# MCU.net
KiCad netlist of a schematic drawn in Altium Designer
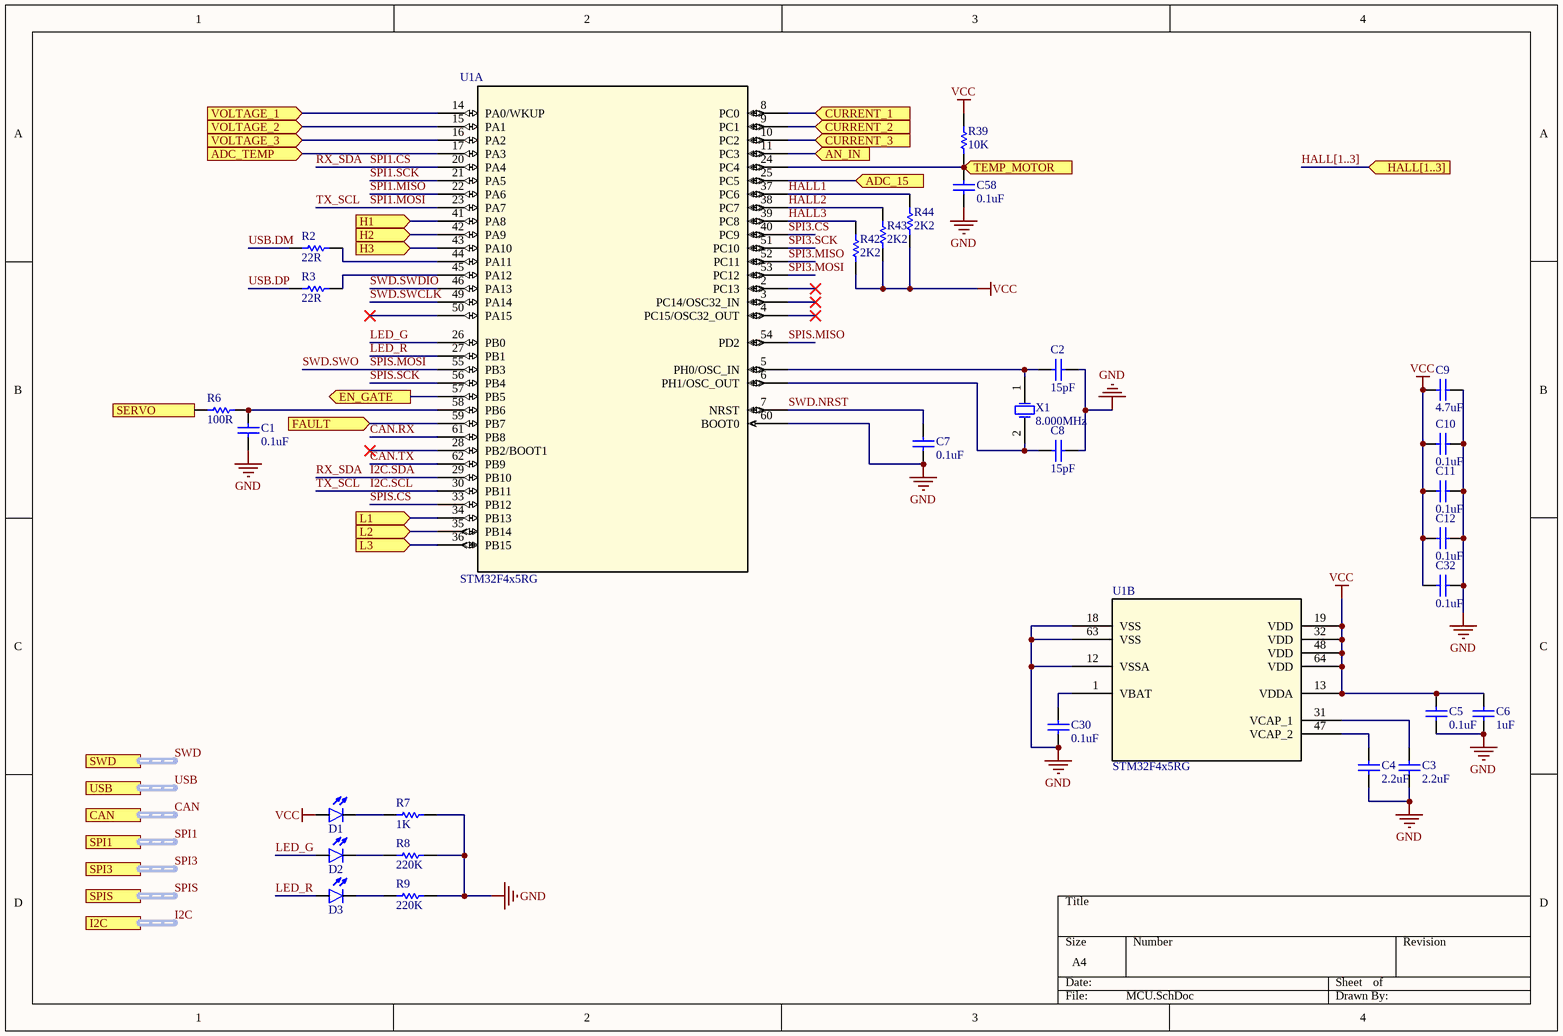
[diagram p0: MCU.SchDoc]

(export (version "E")
  (design (tool "Eeschema 10.0.6"))
  (components
    (comp (ref "C1")
      (value "0.1uF")
      (footprint "C0603[1608X92]")
      (description "0.1uF 16V 10% 0603 (1608 Metric)")
      (fields (field (name "PARTNUMBER") "GCM188R71C104KA37D") (field (name "MANUFACTURER") "Murata"))
      (libsource (lib "Capacitors") (part "CAP_0.1uF_16V_0603_10%"))
    )
    (comp (ref "C2")
      (value "15pF")
      (footprint "C0603[1608X92]")
      (description "15pF 6.3V 1% 0603 (1608 Metric)")
      (fields (field (name "PARTNUMBER") "CBR02C150F9GAC") (field (name "MANUFACTURER") "KEMET"))
      (libsource (lib "Capacitors") (part "CAP_15pF_6.3V_0603_1%"))
    )
    (comp (ref "C3")
      (value "2.2uF")
      (footprint "C1206[3216X160]")
      (description "2.2uF 6.3V 10% 1206 (3216 Metric)")
      (fields (field (name "PARTNUMBER") "GRM31CR60J476KE19L") (field (name "MANUFACTURER") "Murata"))
      (libsource (lib "Capacitors") (part "CAP_2.2uF_16V_1206_10%"))
    )
    (comp (ref "C4")
      (value "2.2uF")
      (footprint "C1206[3216X160]")
      (description "2.2uF 6.3V 10% 1206 (3216 Metric)")
      (fields (field (name "PARTNUMBER") "GRM31CR60J476KE19L") (field (name "MANUFACTURER") "Murata"))
      (libsource (lib "Capacitors") (part "CAP_2.2uF_16V_1206_10%"))
    )
    (comp (ref "C5")
      (value "0.1uF")
      (footprint "C0603[1608X92]")
      (description "0.1uF 6.3V 10% 0603 (1608 Metric)")
      (fields (field (name "PARTNUMBER") "GRM188R70J104KA01D") (field (name "MANUFACTURER") "Murata"))
      (libsource (lib "Capacitors") (part "CAP_0.1uF_6.3V_0603_10%"))
    )
    (comp (ref "C6")
      (value "1uF")
      (footprint "C0603[1608X92]")
      (description "1uF 6.3V 10% 0603 (1608 Metric)")
      (fields (field (name "PARTNUMBER") "GRM188R60J105KA01D") (field (name "MANUFACTURER") "Murata"))
      (libsource (lib "Capacitors") (part "CAP_1uF_6.3V_0603_10%"))
    )
    (comp (ref "C7")
      (value "0.1uF")
      (footprint "C0603[1608X92]")
      (description "0.1uF 6.3V 10% 0603 (1608 Metric)")
      (fields (field (name "PARTNUMBER") "GRM188R70J104KA01D") (field (name "MANUFACTURER") "Murata"))
      (libsource (lib "Capacitors") (part "CAP_0.1uF_6.3V_0603_10%"))
    )
    (comp (ref "C8")
      (value "15pF")
      (footprint "C0603[1608X92]")
      (description "15pF 6.3V 1% 0603 (1608 Metric)")
      (fields (field (name "PARTNUMBER") "CBR02C150F9GAC") (field (name "MANUFACTURER") "KEMET"))
      (libsource (lib "Capacitors") (part "CAP_15pF_6.3V_0603_1%"))
    )
    (comp (ref "C9")
      (value "4.7uF")
      (footprint "C0603[1608X92]")
      (description "4.7uF 6.3V 10% 0603 (1608 Metric)")
      (fields (field (name "PARTNUMBER") "GRM188R60J475KE19D") (field (name "MANUFACTURER") "Murata"))
      (libsource (lib "Capacitors") (part "CAP_4.7uF_6.3V_0603_10%"))
    )
    (comp (ref "C10")
      (value "0.1uF")
      (footprint "C0603[1608X92]")
      (description "0.1uF 6.3V 10% 0603 (1608 Metric)")
      (fields (field (name "PARTNUMBER") "GRM188R70J104KA01D") (field (name "MANUFACTURER") "Murata"))
      (libsource (lib "Capacitors") (part "CAP_0.1uF_6.3V_0603_10%"))
    )
    (comp (ref "C11")
      (value "0.1uF")
      (footprint "C0603[1608X92]")
      (description "0.1uF 6.3V 10% 0603 (1608 Metric)")
      (fields (field (name "PARTNUMBER") "GRM188R70J104KA01D") (field (name "MANUFACTURER") "Murata"))
      (libsource (lib "Capacitors") (part "CAP_0.1uF_6.3V_0603_10%"))
    )
    (comp (ref "C12")
      (value "0.1uF")
      (footprint "C0603[1608X92]")
      (description "0.1uF 6.3V 10% 0603 (1608 Metric)")
      (fields (field (name "PARTNUMBER") "GRM188R70J104KA01D") (field (name "MANUFACTURER") "Murata"))
      (libsource (lib "Capacitors") (part "CAP_0.1uF_6.3V_0603_10%"))
    )
    (comp (ref "C30")
      (value "0.1uF")
      (footprint "C0603[1608X92]")
      (description "0.1uF 6.3V 10% 0603 (1608 Metric)")
      (fields (field (name "PARTNUMBER") "GRM188R70J104KA01D") (field (name "MANUFACTURER") "Murata"))
      (libsource (lib "Capacitors") (part "CAP_0.1uF_6.3V_0603_10%"))
    )
    (comp (ref "C32")
      (value "0.1uF")
      (footprint "C0603[1608X92]")
      (description "0.1uF 6.3V 10% 0603 (1608 Metric)")
      (fields (field (name "PARTNUMBER") "GRM188R70J104KA01D") (field (name "MANUFACTURER") "Murata"))
      (libsource (lib "Capacitors") (part "CAP_0.1uF_6.3V_0603_10%"))
    )
    (comp (ref "C58")
      (value "0.1uF")
      (footprint "C0603[1608X92]")
      (description "0.1uF 6.3V 10% 0603 (1608 Metric)")
      (fields (field (name "PARTNUMBER") "GRM188R70J104KA01D") (field (name "MANUFACTURER") "Murata"))
      (libsource (lib "Capacitors") (part "CAP_0.1uF_6.3V_0603_10%"))
    )
    (comp (ref "D1")
      (value "LED_0603_BLUE_5mA")
      (footprint "LED0603")
      (fields (field (name "PARTNUMBER") "LTST-C193TBKT-5A") (field (name "MANUFACTURER") "Lite-On Inc."))
      (libsource (lib "LEDs") (part "LED_0603_BLUE_5mA"))
    )
    (comp (ref "D2")
      (value "LED_0603_GREEN_5mA")
      (footprint "LED0603")
      (fields (field (name "PARTNUMBER") "LTST-C193TGKT-5A") (field (name "MANUFACTURER") "Lite-On Inc."))
      (libsource (lib "LEDs") (part "LED_0603_GREEN_5mA"))
    )
    (comp (ref "D3")
      (value "LED_0603_ORANGE_5mA")
      (footprint "LED0603")
      (fields (field (name "PARTNUMBER") "LTST-C193KFKT-5A") (field (name "MANUFACTURER") "Lite-On Inc."))
      (libsource (lib "LEDs") (part "LED_0603_ORANGE_5mA"))
    )
    (comp (ref "R2")
      (value "22R")
      (footprint "R0603[1608]")
      (description "22R 0.25W 1% 0603 (1005 Metric)")
      (fields (field (name "MANUFACTURER") "Vishay / Dale") (field (name "PARTNUMBER") "CRCW060322R0FKEAHP"))
      (libsource (lib "Resistors") (part "RES_22R_0603_1%"))
    )
    (comp (ref "R3")
      (value "22R")
      (footprint "R0603[1608]")
      (description "22R 0.25W 1% 0603 (1005 Metric)")
      (fields (field (name "MANUFACTURER") "Vishay / Dale") (field (name "PARTNUMBER") "CRCW060322R0FKEAHP"))
      (libsource (lib "Resistors") (part "RES_22R_0603_1%"))
    )
    (comp (ref "R6")
      (value "100R")
      (footprint "R0603[1608]")
      (description "100R 0.25W 1% 0603 (1005 Metric)")
      (fields (field (name "MANUFACTURER") "Vishay / Dale") (field (name "PARTNUMBER") "CRCW0603100RFKEAHP"))
      (libsource (lib "Resistors") (part "RES_100R_0603_1%"))
    )
    (comp (ref "R7")
      (value "1K")
      (footprint "R0603[1608]")
      (description "1K 0.25W 1% 0603 (1005 Metric)")
      (fields (field (name "MANUFACTURER") "Vishay / Dale") (field (name "PARTNUMBER") "CRCW06031K00FKEAHP"))
      (libsource (lib "Resistors") (part "RES_1K_0603_1%"))
    )
    (comp (ref "R8")
      (value "220K")
      (footprint "R0603[1608]")
      (description "220K 0.25W 1% 0603 (1005 Metric)")
      (fields (field (name "MANUFACTURER") "Vishay / Dale") (field (name "PARTNUMBER") "CRCW0603220KJNEAHP"))
      (libsource (lib "Resistors") (part "RES_220K_0603_1%"))
    )
    (comp (ref "R9")
      (value "220K")
      (footprint "R0603[1608]")
      (description "220K 0.25W 1% 0603 (1005 Metric)")
      (fields (field (name "MANUFACTURER") "Vishay / Dale") (field (name "PARTNUMBER") "CRCW0603220KJNEAHP"))
      (libsource (lib "Resistors") (part "RES_220K_0603_1%"))
    )
    (comp (ref "R39")
      (value "10K")
      (footprint "R0603[1608]")
      (description "10K 0.25W 1% 0603 (1005 Metric)")
      (fields (field (name "MANUFACTURER") "Vishay") (field (name "PARTNUMBER") "RCS060310K0FKEA"))
      (libsource (lib "Resistors") (part "RES_10K_0603_1%"))
    )
    (comp (ref "R42")
      (value "2K2")
      (footprint "R0603[1608]")
      (description "2K2 0.25W 1% 0603 (1005 Metric)")
      (fields (field (name "MANUFACTURER") "Vishay / Dale") (field (name "PARTNUMBER") "CRCW06032K20FKEAHP"))
      (libsource (lib "Resistors") (part "RES_2K2_0603_1%"))
    )
    (comp (ref "R43")
      (value "2K2")
      (footprint "R0603[1608]")
      (description "2K2 0.25W 1% 0603 (1005 Metric)")
      (fields (field (name "MANUFACTURER") "Vishay / Dale") (field (name "PARTNUMBER") "CRCW06032K20FKEAHP"))
      (libsource (lib "Resistors") (part "RES_2K2_0603_1%"))
    )
    (comp (ref "R44")
      (value "2K2")
      (footprint "R0603[1608]")
      (description "2K2 0.25W 1% 0603 (1005 Metric)")
      (fields (field (name "MANUFACTURER") "Vishay / Dale") (field (name "PARTNUMBER") "CRCW06032K20FKEAHP"))
      (libsource (lib "Resistors") (part "RES_2K2_0603_1%"))
    )
    (comp (ref "U1")
      (value "STM32F4x5RG")
      (footprint "LQFP64-10x10mm")
      (description "Imported")
      (fields (field (name "PARTNUMBER") "STM32F405RG") (field (name "MANUFACTURER") "STMicroelectronics"))
      (libsource (lib "General_Component") (part "STM32F4x5RG"))
    )
    (comp (ref "X1")
      (value "8.000MHz")
      (footprint "OSC_2SM_3R2x2R5")
      (description "Crystal Oscillator")
      (fields (field (name "MANUFACTURER") "NX") (field (name "PARTNUMBER") "NX3225GD-8.000M-EXS00A-CG04874"))
      (libsource (lib "General_Component") (part "XTAL"))
    )
  )
  (nets
    (net (code "8") (name "/ADC_15") (class "Default")
      (node (ref "U1") (pin "25") (pinfunction "PC5_25") (pintype "bidirectional"))
    )
    (net (code "9") (name "/ADC_TEMP") (class "Default")
      (node (ref "U1") (pin "17") (pinfunction "PA3_17") (pintype "bidirectional"))
    )
    (net (code "10") (name "/AN_IN") (class "Default")
      (node (ref "U1") (pin "11") (pinfunction "PC3_11") (pintype "bidirectional"))
    )
    (net (code "11") (name "/CAN.RX") (class "Default")
      (node (ref "U1") (pin "61") (pinfunction "PB8_61") (pintype "bidirectional"))
    )
    (net (code "12") (name "/CAN.TX") (class "Default")
      (node (ref "U1") (pin "62") (pinfunction "PB9_62") (pintype "bidirectional"))
    )
    (net (code "13") (name "/CURRENT_1") (class "Default")
      (node (ref "U1") (pin "8") (pinfunction "PC0_8") (pintype "bidirectional"))
    )
    (net (code "14") (name "/CURRENT_2") (class "Default")
      (node (ref "U1") (pin "9") (pinfunction "PC1_9") (pintype "bidirectional"))
    )
    (net (code "15") (name "/CURRENT_3") (class "Default")
      (node (ref "U1") (pin "10") (pinfunction "PC2_10") (pintype "bidirectional"))
    )
    (net (code "16") (name "/EN_GATE") (class "Default")
      (node (ref "U1") (pin "57") (pinfunction "PB5_57") (pintype "bidirectional"))
    )
    (net (code "17") (name "/FAULT") (class "Default")
      (node (ref "U1") (pin "59") (pinfunction "PB7_59") (pintype "bidirectional"))
    )
    (net (code "18") (name "/H1") (class "Default")
      (node (ref "U1") (pin "41") (pinfunction "PA8_41") (pintype "bidirectional"))
    )
    (net (code "19") (name "/H2") (class "Default")
      (node (ref "U1") (pin "42") (pinfunction "PA9_42") (pintype "bidirectional"))
    )
    (net (code "20") (name "/H3") (class "Default")
      (node (ref "U1") (pin "43") (pinfunction "PA10_43") (pintype "bidirectional"))
    )
    (net (code "21") (name "/HALL1") (class "Default")
      (node (ref "R44") (pin "2") (pinfunction "2_2") (pintype "passive"))
      (node (ref "U1") (pin "37") (pinfunction "PC6_37") (pintype "bidirectional"))
    )
    (net (code "22") (name "/HALL2") (class "Default")
      (node (ref "R43") (pin "2") (pinfunction "2_2") (pintype "passive"))
      (node (ref "U1") (pin "38") (pinfunction "PC7_38") (pintype "bidirectional"))
    )
    (net (code "23") (name "/HALL3") (class "Default")
      (node (ref "R42") (pin "2") (pinfunction "2_2") (pintype "passive"))
      (node (ref "U1") (pin "39") (pinfunction "PC8_39") (pintype "bidirectional"))
    )
    (net (code "25") (name "/I2C.SCL") (class "Default")
      (node (ref "U1") (pin "23") (pinfunction "PA7_23") (pintype "bidirectional"))
      (node (ref "U1") (pin "30") (pinfunction "PB11_30") (pintype "bidirectional"))
    )
    (net (code "26") (name "/I2C.SDA") (class "Default")
      (node (ref "U1") (pin "20") (pinfunction "PA4_20") (pintype "bidirectional"))
      (node (ref "U1") (pin "29") (pinfunction "PB10_29") (pintype "bidirectional"))
    )
    (net (code "27") (name "/L1") (class "Default")
      (node (ref "U1") (pin "34") (pinfunction "PB13_34") (pintype "bidirectional"))
    )
    (net (code "28") (name "/L2") (class "Default")
      (node (ref "U1") (pin "35") (pinfunction "PB14_35") (pintype "bidirectional"))
    )
    (net (code "29") (name "/L3") (class "Default")
      (node (ref "U1") (pin "36") (pinfunction "PB15_36") (pintype "bidirectional"))
    )
    (net (code "30") (name "/LED_G") (class "Default")
      (node (ref "D2") (pin "A") (pinfunction "A_A") (pintype "passive"))
      (node (ref "U1") (pin "26") (pinfunction "PB0_26") (pintype "bidirectional"))
    )
    (net (code "31") (name "/LED_R") (class "Default")
      (node (ref "D3") (pin "A") (pinfunction "A_A") (pintype "passive"))
      (node (ref "U1") (pin "27") (pinfunction "PB1_27") (pintype "bidirectional"))
    )
    (net (code "32") (name "/SERVO") (class "Default")
      (node (ref "R6") (pin "1") (pinfunction "1_1") (pintype "passive"))
    )
    (net (code "33") (name "/SPI1.MISO") (class "Default")
      (node (ref "U1") (pin "22") (pinfunction "PA6_22") (pintype "bidirectional"))
    )
    (net (code "34") (name "/SPI1.SCK") (class "Default")
      (node (ref "U1") (pin "21") (pinfunction "PA5_21") (pintype "bidirectional"))
    )
    (net (code "35") (name "/SPI3.CS") (class "Default")
      (node (ref "U1") (pin "40") (pinfunction "PC9_40") (pintype "bidirectional"))
    )
    (net (code "36") (name "/SPI3.MISO") (class "Default")
      (node (ref "U1") (pin "52") (pinfunction "PC11_52") (pintype "bidirectional"))
    )
    (net (code "37") (name "/SPI3.MOSI") (class "Default")
      (node (ref "U1") (pin "53") (pinfunction "PC12_53") (pintype "bidirectional"))
    )
    (net (code "38") (name "/SPI3.SCK") (class "Default")
      (node (ref "U1") (pin "51") (pinfunction "PC10_51") (pintype "bidirectional"))
    )
    (net (code "39") (name "/SPIS.CS") (class "Default")
      (node (ref "U1") (pin "33") (pinfunction "PB12_33") (pintype "bidirectional"))
    )
    (net (code "40") (name "/SPIS.MISO") (class "Default")
      (node (ref "U1") (pin "54") (pinfunction "PD2_54") (pintype "bidirectional"))
    )
    (net (code "41") (name "/SPIS.MOSI") (class "Default")
      (node (ref "U1") (pin "55") (pinfunction "PB3_55") (pintype "bidirectional"))
    )
    (net (code "42") (name "/SPIS.SCK") (class "Default")
      (node (ref "U1") (pin "56") (pinfunction "PB4_56") (pintype "bidirectional"))
    )
    (net (code "43") (name "/SWD.NRST") (class "Default")
      (node (ref "C7") (pin "1") (pinfunction "1_1") (pintype "passive"))
      (node (ref "U1") (pin "7") (pinfunction "NRST_7") (pintype "bidirectional"))
    )
    (net (code "44") (name "/SWD.SWCLK") (class "Default")
      (node (ref "U1") (pin "49") (pinfunction "PA14_49") (pintype "bidirectional"))
    )
    (net (code "45") (name "/SWD.SWDIO") (class "Default")
      (node (ref "U1") (pin "46") (pinfunction "PA13_46") (pintype "bidirectional"))
    )
    (net (code "46") (name "/TEMP_MOTOR") (class "Default")
      (node (ref "C58") (pin "1") (pinfunction "1_1") (pintype "passive"))
      (node (ref "R39") (pin "1") (pinfunction "1_1") (pintype "passive"))
      (node (ref "U1") (pin "24") (pinfunction "PC4_24") (pintype "bidirectional"))
    )
    (net (code "47") (name "/USB.DM") (class "Default")
      (node (ref "R2") (pin "1") (pinfunction "1_1") (pintype "passive"))
    )
    (net (code "48") (name "/USB.DP") (class "Default")
      (node (ref "R3") (pin "1") (pinfunction "1_1") (pintype "passive"))
    )
    (net (code "49") (name "/VOLTAGE_1") (class "Default")
      (node (ref "U1") (pin "14") (pinfunction "PA0/WKUP_14") (pintype "bidirectional"))
    )
    (net (code "50") (name "/VOLTAGE_2") (class "Default")
      (node (ref "U1") (pin "15") (pinfunction "PA1_15") (pintype "bidirectional"))
    )
    (net (code "51") (name "/VOLTAGE_3") (class "Default")
      (node (ref "U1") (pin "16") (pinfunction "PA2_16") (pintype "bidirectional"))
    )
    (net (code "59") (name "GND") (class "Default")
      (node (ref "C1") (pin "1") (pinfunction "1_1") (pintype "passive"))
      (node (ref "C10") (pin "2") (pinfunction "2_2") (pintype "passive"))
      (node (ref "C11") (pin "2") (pinfunction "2_2") (pintype "passive"))
      (node (ref "C12") (pin "2") (pinfunction "2_2") (pintype "passive"))
      (node (ref "C2") (pin "2") (pinfunction "2_2") (pintype "passive"))
      (node (ref "C3") (pin "1") (pinfunction "1_1") (pintype "passive"))
      (node (ref "C30") (pin "1") (pinfunction "1_1") (pintype "passive"))
      (node (ref "C32") (pin "2") (pinfunction "2_2") (pintype "passive"))
      (node (ref "C4") (pin "1") (pinfunction "1_1") (pintype "passive"))
      (node (ref "C5") (pin "2") (pinfunction "2_2") (pintype "passive"))
      (node (ref "C58") (pin "2") (pinfunction "2_2") (pintype "passive"))
      (node (ref "C6") (pin "2") (pinfunction "2_2") (pintype "passive"))
      (node (ref "C7") (pin "2") (pinfunction "2_2") (pintype "passive"))
      (node (ref "C8") (pin "2") (pinfunction "2_2") (pintype "passive"))
      (node (ref "C9") (pin "2") (pinfunction "2_2") (pintype "passive"))
      (node (ref "R7") (pin "2") (pinfunction "2_2") (pintype "passive"))
      (node (ref "R8") (pin "2") (pinfunction "2_2") (pintype "passive"))
      (node (ref "R9") (pin "2") (pinfunction "2_2") (pintype "passive"))
      (node (ref "U1") (pin "12") (pinfunction "VSSA_12") (pintype "power_in"))
      (node (ref "U1") (pin "18") (pinfunction "VSS_18") (pintype "power_in"))
      (node (ref "U1") (pin "60") (pinfunction "BOOT0_60") (pintype "input"))
      (node (ref "U1") (pin "63") (pinfunction "VSS_63") (pintype "power_in"))
    )
    (net (code "60") (name "Net-(D1-PadC)") (class "Default")
      (node (ref "D1") (pin "C") (pinfunction "C_C") (pintype "passive"))
      (node (ref "R7") (pin "1") (pinfunction "1_1") (pintype "passive"))
    )
    (net (code "61") (name "Net-(D2-PadC)") (class "Default")
      (node (ref "D2") (pin "C") (pinfunction "C_C") (pintype "passive"))
      (node (ref "R8") (pin "1") (pinfunction "1_1") (pintype "passive"))
    )
    (net (code "62") (name "Net-(D3-PadC)") (class "Default")
      (node (ref "D3") (pin "C") (pinfunction "C_C") (pintype "passive"))
      (node (ref "R9") (pin "1") (pinfunction "1_1") (pintype "passive"))
    )
    (net (code "63") (name "Net-(U1A-PA11)") (class "Default")
      (node (ref "R2") (pin "2") (pinfunction "2_2") (pintype "passive"))
      (node (ref "U1") (pin "44") (pinfunction "PA11_44") (pintype "bidirectional"))
    )
    (net (code "64") (name "Net-(U1A-PA12)") (class "Default")
      (node (ref "R3") (pin "2") (pinfunction "2_2") (pintype "passive"))
      (node (ref "U1") (pin "45") (pinfunction "PA12_45") (pintype "bidirectional"))
    )
    (net (code "65") (name "Net-(U1A-PB6)") (class "Default")
      (node (ref "C1") (pin "2") (pinfunction "2_2") (pintype "passive"))
      (node (ref "R6") (pin "2") (pinfunction "2_2") (pintype "passive"))
      (node (ref "U1") (pin "58") (pinfunction "PB6_58") (pintype "bidirectional"))
    )
    (net (code "66") (name "Net-(U1A-PH0{slash}OSC_IN)") (class "Default")
      (node (ref "C2") (pin "1") (pinfunction "1_1") (pintype "passive"))
      (node (ref "U1") (pin "5") (pinfunction "PH0/OSC_IN_5") (pintype "bidirectional"))
      (node (ref "X1") (pin "1") (pinfunction "OSC1_1") (pintype "passive"))
    )
    (net (code "67") (name "Net-(U1A-PH1{slash}OSC_OUT)") (class "Default")
      (node (ref "C8") (pin "1") (pinfunction "1_1") (pintype "passive"))
      (node (ref "U1") (pin "6") (pinfunction "PH1/OSC_OUT_6") (pintype "bidirectional"))
      (node (ref "X1") (pin "2") (pinfunction "OSC2_2") (pintype "passive"))
    )
    (net (code "68") (name "Net-(U1B-VBAT)") (class "Default")
      (node (ref "C30") (pin "2") (pinfunction "2_2") (pintype "passive"))
      (node (ref "U1") (pin "1") (pinfunction "VBAT_1") (pintype "power_in"))
    )
    (net (code "69") (name "Net-(U1B-VCAP_1)") (class "Default")
      (node (ref "C3") (pin "2") (pinfunction "2_2") (pintype "passive"))
      (node (ref "U1") (pin "31") (pinfunction "VCAP_1_31") (pintype "power_in"))
    )
    (net (code "70") (name "Net-(U1B-VCAP_2)") (class "Default")
      (node (ref "C4") (pin "2") (pinfunction "2_2") (pintype "passive"))
      (node (ref "U1") (pin "47") (pinfunction "VCAP_2_47") (pintype "power_in"))
    )
    (net (code "71") (name "VCC") (class "Default")
      (node (ref "C10") (pin "1") (pinfunction "1_1") (pintype "passive"))
      (node (ref "C11") (pin "1") (pinfunction "1_1") (pintype "passive"))
      (node (ref "C12") (pin "1") (pinfunction "1_1") (pintype "passive"))
      (node (ref "C32") (pin "1") (pinfunction "1_1") (pintype "passive"))
      (node (ref "C5") (pin "1") (pinfunction "1_1") (pintype "passive"))
      (node (ref "C6") (pin "1") (pinfunction "1_1") (pintype "passive"))
      (node (ref "C9") (pin "1") (pinfunction "1_1") (pintype "passive"))
      (node (ref "D1") (pin "A") (pinfunction "A_A") (pintype "passive"))
      (node (ref "R39") (pin "2") (pinfunction "2_2") (pintype "passive"))
      (node (ref "R42") (pin "1") (pinfunction "1_1") (pintype "passive"))
      (node (ref "R43") (pin "1") (pinfunction "1_1") (pintype "passive"))
      (node (ref "R44") (pin "1") (pinfunction "1_1") (pintype "passive"))
      (node (ref "U1") (pin "13") (pinfunction "VDDA_13") (pintype "power_in"))
      (node (ref "U1") (pin "19") (pinfunction "VDD_19") (pintype "power_in"))
      (node (ref "U1") (pin "32") (pinfunction "VDD_32") (pintype "power_in"))
      (node (ref "U1") (pin "48") (pinfunction "VDD_48") (pintype "power_in"))
      (node (ref "U1") (pin "64") (pinfunction "VDD_64") (pintype "power_in"))
    )
    (net (code "72") (name "unconnected-(U1A-PA15-Pad50)") (class "Default")
      (node (ref "U1") (pin "50") (pinfunction "PA15_50") (pintype "bidirectional+no_connect"))
    )
    (net (code "73") (name "unconnected-(U1A-PB2{slash}BOOT1-Pad28)") (class "Default")
      (node (ref "U1") (pin "28") (pinfunction "PB2/BOOT1_28") (pintype "bidirectional+no_connect"))
    )
    (net (code "74") (name "unconnected-(U1A-PC13-Pad2)") (class "Default")
      (node (ref "U1") (pin "2") (pinfunction "PC13_2") (pintype "bidirectional+no_connect"))
    )
    (net (code "75") (name "unconnected-(U1A-PC14{slash}OSC32_IN-Pad3)") (class "Default")
      (node (ref "U1") (pin "3") (pinfunction "PC14/OSC32_IN_3") (pintype "bidirectional+no_connect"))
    )
    (net (code "76") (name "unconnected-(U1A-PC15{slash}OSC32_OUT-Pad4)") (class "Default")
      (node (ref "U1") (pin "4") (pinfunction "PC15/OSC32_OUT_4") (pintype "bidirectional+no_connect"))
    )
  )
)
